# HM_Core.net
KiCad netlist of a schematic drawn in EAGLE
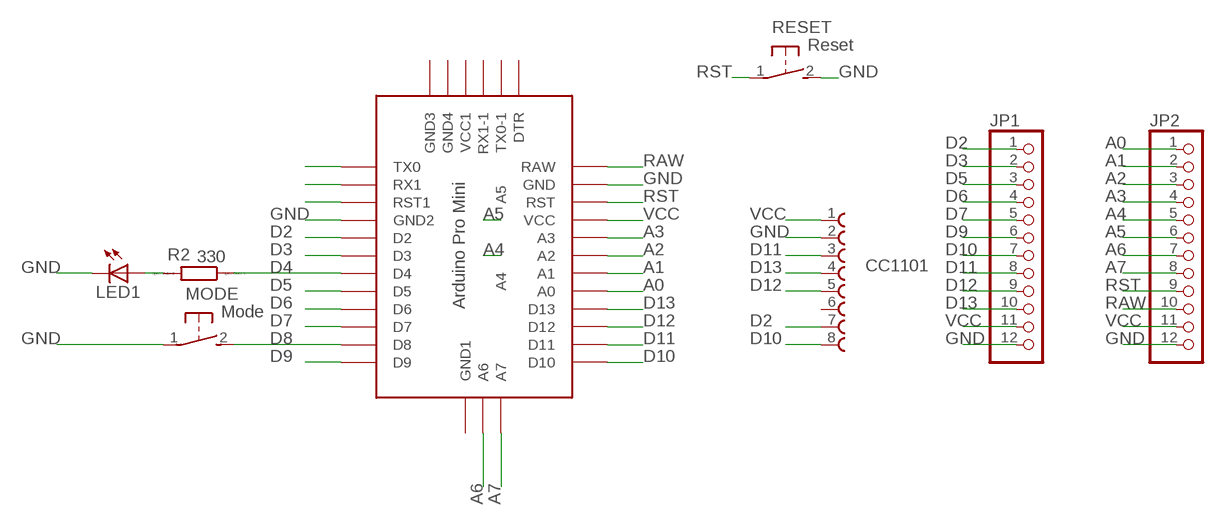
[diagram p0: schematic, sheet 1]

(export (version "E")
  (design (tool "Eeschema 10.0.6"))
  (components
    (comp (ref "CC1101")
      (value "62000811121")
      (footprint "eagle-import:62000811121")
      (libsource (lib "eagle-import") (part "62000811121"))
    )
    (comp (ref "JP1")
      (value "PINHD-1X12")
      (footprint "eagle-import:1X12")
      (libsource (lib "eagle-import") (part "PINHD-1X12"))
    )
    (comp (ref "JP2")
      (value "PINHD-1X12")
      (footprint "eagle-import:1X12")
      (libsource (lib "eagle-import") (part "PINHD-1X12"))
    )
    (comp (ref "LED1")
      (value "LED3MM")
      (footprint "eagle-import:LED3MM")
      (libsource (lib "eagle-import") (part "LED3MM"))
    )
    (comp (ref "MODE")
      (value "Mode")
      (footprint "eagle-import:B3F-31XX")
      (fields (field (name "MPN") "B3F-3100"))
      (libsource (lib "eagle-import") (part "31-XX"))
    )
    (comp (ref "R2")
      (value "330")
      (footprint "eagle-import:0207_10")
      (libsource (lib "eagle-import") (part "R0207/10"))
    )
    (comp (ref "RESET")
      (value "Reset")
      (footprint "eagle-import:B3F-31XX")
      (fields (field (name "MPN") "B3F-3100"))
      (libsource (lib "eagle-import") (part "31-XX"))
    )
    (comp (ref "U$1")
      (value "ABK-PRO-MINI")
      (footprint "eagle-import:ABK-PRO-MINI")
      (libsource (lib "eagle-import") (part "ABK-PRO-MINI"))
    )
  )
  (nets
    (net (code "1") (name "/A0") (class "Default")
      (node (ref "JP2") (pin "1") (pinfunction "1_1") (pintype "passive"))
      (node (ref "U$1") (pin "A0") (pinfunction "A0_A0") (pintype "bidirectional"))
    )
    (net (code "2") (name "/A1") (class "Default")
      (node (ref "JP2") (pin "2") (pinfunction "2_2") (pintype "passive"))
      (node (ref "U$1") (pin "A1") (pinfunction "A1_A1") (pintype "bidirectional"))
    )
    (net (code "3") (name "/A2") (class "Default")
      (node (ref "JP2") (pin "3") (pinfunction "3_3") (pintype "passive"))
      (node (ref "U$1") (pin "A2") (pinfunction "A2_A2") (pintype "bidirectional"))
    )
    (net (code "4") (name "/A3") (class "Default")
      (node (ref "JP2") (pin "4") (pinfunction "4_4") (pintype "passive"))
      (node (ref "U$1") (pin "A3") (pinfunction "A3_A3") (pintype "bidirectional"))
    )
    (net (code "5") (name "/A4") (class "Default")
      (node (ref "JP2") (pin "5") (pinfunction "5_5") (pintype "passive"))
      (node (ref "U$1") (pin "A4") (pinfunction "A4_A4") (pintype "bidirectional"))
    )
    (net (code "6") (name "/A5") (class "Default")
      (node (ref "JP2") (pin "6") (pinfunction "6_6") (pintype "passive"))
      (node (ref "U$1") (pin "A5") (pinfunction "A5_A5") (pintype "bidirectional"))
    )
    (net (code "7") (name "/A6") (class "Default")
      (node (ref "JP2") (pin "7") (pinfunction "7_7") (pintype "passive"))
      (node (ref "U$1") (pin "A6") (pinfunction "A6_A6") (pintype "bidirectional"))
    )
    (net (code "8") (name "/A7") (class "Default")
      (node (ref "JP2") (pin "8") (pinfunction "8_8") (pintype "passive"))
      (node (ref "U$1") (pin "A7") (pinfunction "A7_A7") (pintype "bidirectional"))
    )
    (net (code "9") (name "/D2") (class "Default")
      (node (ref "CC1101") (pin "7") (pinfunction "7_7") (pintype "passive"))
      (node (ref "JP1") (pin "1") (pinfunction "1_1") (pintype "passive"))
      (node (ref "U$1") (pin "D2") (pinfunction "D2_D2") (pintype "bidirectional"))
    )
    (net (code "10") (name "/D3") (class "Default")
      (node (ref "JP1") (pin "2") (pinfunction "2_2") (pintype "passive"))
      (node (ref "U$1") (pin "D3") (pinfunction "D3_D3") (pintype "bidirectional"))
    )
    (net (code "11") (name "/D4") (class "Default")
      (node (ref "R2") (pin "1") (pinfunction "1_1") (pintype "passive"))
      (node (ref "U$1") (pin "D4") (pinfunction "D4_D4") (pintype "bidirectional"))
    )
    (net (code "12") (name "/D5") (class "Default")
      (node (ref "JP1") (pin "3") (pinfunction "3_3") (pintype "passive"))
      (node (ref "U$1") (pin "D5") (pinfunction "D5_D5") (pintype "bidirectional"))
    )
    (net (code "13") (name "/D6") (class "Default")
      (node (ref "JP1") (pin "4") (pinfunction "4_4") (pintype "passive"))
      (node (ref "U$1") (pin "D6") (pinfunction "D6_D6") (pintype "bidirectional"))
    )
    (net (code "14") (name "/D7") (class "Default")
      (node (ref "JP1") (pin "5") (pinfunction "5_5") (pintype "passive"))
      (node (ref "U$1") (pin "D7") (pinfunction "D7_D7") (pintype "bidirectional"))
    )
    (net (code "15") (name "/D8") (class "Default")
      (node (ref "MODE") (pin "2") (pinfunction "S_2") (pintype "passive"))
      (node (ref "U$1") (pin "D8") (pinfunction "D8_D8") (pintype "bidirectional"))
    )
    (net (code "16") (name "/D9") (class "Default")
      (node (ref "JP1") (pin "6") (pinfunction "6_6") (pintype "passive"))
      (node (ref "U$1") (pin "D9") (pinfunction "D9_D9") (pintype "bidirectional"))
    )
    (net (code "17") (name "/D10") (class "Default")
      (node (ref "CC1101") (pin "8") (pinfunction "8_8") (pintype "passive"))
      (node (ref "JP1") (pin "7") (pinfunction "7_7") (pintype "passive"))
      (node (ref "U$1") (pin "D10") (pinfunction "D10_D10") (pintype "bidirectional"))
    )
    (net (code "18") (name "/D11") (class "Default")
      (node (ref "CC1101") (pin "3") (pinfunction "3_3") (pintype "passive"))
      (node (ref "JP1") (pin "8") (pinfunction "8_8") (pintype "passive"))
      (node (ref "U$1") (pin "D11") (pinfunction "D11_D11") (pintype "bidirectional"))
    )
    (net (code "19") (name "/D12") (class "Default")
      (node (ref "CC1101") (pin "5") (pinfunction "5_5") (pintype "passive"))
      (node (ref "JP1") (pin "9") (pinfunction "9_9") (pintype "passive"))
      (node (ref "U$1") (pin "D12") (pinfunction "D12_D12") (pintype "bidirectional"))
    )
    (net (code "20") (name "/D13") (class "Default")
      (node (ref "CC1101") (pin "4") (pinfunction "4_4") (pintype "passive"))
      (node (ref "JP1") (pin "10") (pinfunction "10_10") (pintype "passive"))
      (node (ref "U$1") (pin "D13") (pinfunction "D13_D13") (pintype "bidirectional"))
    )
    (net (code "21") (name "/GND") (class "Default")
      (node (ref "CC1101") (pin "2") (pinfunction "2_2") (pintype "passive"))
      (node (ref "JP1") (pin "12") (pinfunction "12_12") (pintype "passive"))
      (node (ref "JP2") (pin "12") (pinfunction "12_12") (pintype "passive"))
      (node (ref "LED1") (pin "K") (pinfunction "C_K") (pintype "passive"))
      (node (ref "MODE") (pin "1") (pinfunction "P_1") (pintype "passive"))
      (node (ref "RESET") (pin "2") (pinfunction "S_2") (pintype "passive"))
      (node (ref "U$1") (pin "GND") (pinfunction "GND_GND") (pintype "bidirectional"))
      (node (ref "U$1") (pin "GND1") (pinfunction "GND2_GND1") (pintype "bidirectional"))
    )
    (net (code "22") (name "/RAW") (class "Default")
      (node (ref "JP2") (pin "10") (pinfunction "10_10") (pintype "passive"))
      (node (ref "U$1") (pin "RAW") (pinfunction "RAW_RAW") (pintype "bidirectional"))
    )
    (net (code "23") (name "/RST") (class "Default")
      (node (ref "JP2") (pin "9") (pinfunction "9_9") (pintype "passive"))
      (node (ref "RESET") (pin "1") (pinfunction "P_1") (pintype "passive"))
      (node (ref "U$1") (pin "RST") (pinfunction "RST_RST") (pintype "bidirectional"))
    )
    (net (code "24") (name "/VCC") (class "Default")
      (node (ref "CC1101") (pin "1") (pinfunction "1_1") (pintype "passive"))
      (node (ref "JP1") (pin "11") (pinfunction "11_11") (pintype "passive"))
      (node (ref "JP2") (pin "11") (pinfunction "11_11") (pintype "passive"))
      (node (ref "U$1") (pin "VCC") (pinfunction "VCC_VCC") (pintype "bidirectional"))
    )
    (net (code "25") (name "Net-(LED1-PadA)") (class "Default")
      (node (ref "LED1") (pin "A") (pinfunction "A_A") (pintype "passive"))
      (node (ref "R2") (pin "2") (pinfunction "2_2") (pintype "passive"))
    )
    (net (code "26") (name "unconnected-(CC1101-Pad6)") (class "Default")
      (node (ref "CC1101") (pin "6") (pinfunction "6_6") (pintype "passive"))
    )
    (net (code "27") (name "unconnected-(U$1-GND1-PadGND4)") (class "Default")
      (node (ref "U$1") (pin "GND4") (pinfunction "GND1_GND4") (pintype "bidirectional"))
    )
    (net (code "28") (name "unconnected-(U$1-GND3-PadGND2)") (class "Default")
      (node (ref "U$1") (pin "GND2") (pinfunction "GND3_GND2") (pintype "bidirectional"))
    )
    (net (code "29") (name "unconnected-(U$1-GND4-PadGND3)") (class "Default")
      (node (ref "U$1") (pin "GND3") (pinfunction "GND4_GND3") (pintype "bidirectional"))
    )
    (net (code "30") (name "unconnected-(U$1-PadDTR)") (class "Default")
      (node (ref "U$1") (pin "DTR") (pinfunction "DTR_DTR") (pintype "bidirectional"))
    )
    (net (code "31") (name "unconnected-(U$1-PadRST1)") (class "Default")
      (node (ref "U$1") (pin "RST1") (pinfunction "RST1_RST1") (pintype "bidirectional"))
    )
    (net (code "32") (name "unconnected-(U$1-PadRX1)") (class "Default")
      (node (ref "U$1") (pin "RX1") (pinfunction "RX1_RX1") (pintype "bidirectional"))
    )
    (net (code "33") (name "unconnected-(U$1-PadRX1-1)") (class "Default")
      (node (ref "U$1") (pin "RX1-1") (pinfunction "RX1-1_RX1-1") (pintype "bidirectional"))
    )
    (net (code "34") (name "unconnected-(U$1-PadTX0)") (class "Default")
      (node (ref "U$1") (pin "TX0") (pinfunction "TX0_TX0") (pintype "bidirectional"))
    )
    (net (code "35") (name "unconnected-(U$1-PadTX0-1)") (class "Default")
      (node (ref "U$1") (pin "TX0-1") (pinfunction "TX0-1_TX0-1") (pintype "bidirectional"))
    )
    (net (code "36") (name "unconnected-(U$1-PadVCC1)") (class "Default")
      (node (ref "U$1") (pin "VCC1") (pinfunction "VCC1_VCC1") (pintype "bidirectional"))
    )
  )
)
